# docking_station_with_STLink.net
KiCad netlist of a schematic drawn in Altium Designer
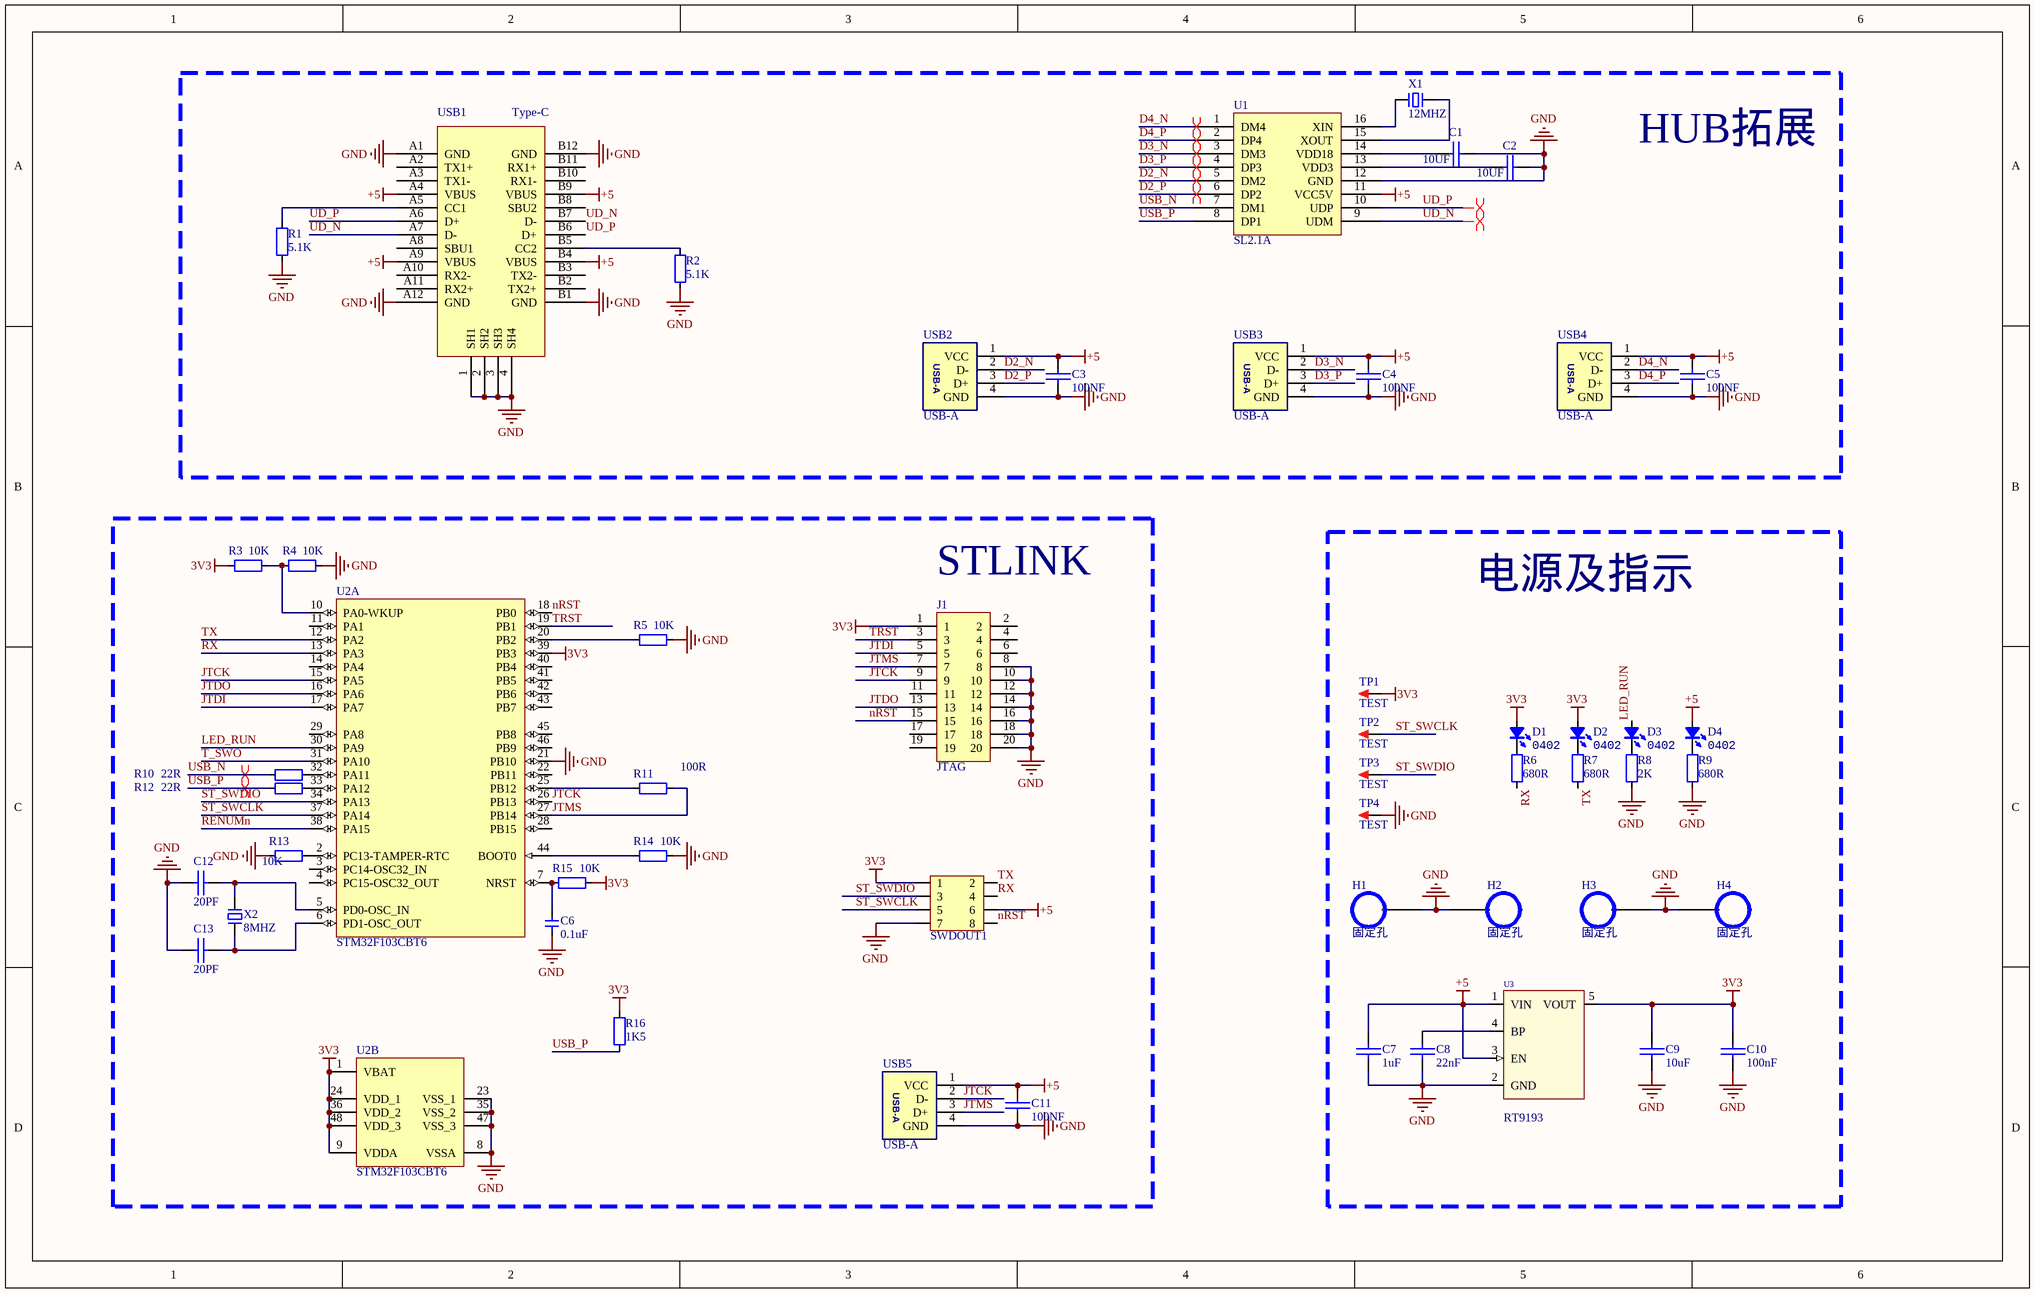
[diagram p0: docking_station_with_STLink.SchDoc]

(export (version "E")
  (design (tool "Eeschema 10.0.6"))
  (components
    (comp (ref "C1")
      (value "10UF")
      (footprint "0603C")
      (description "无极性电容")
      (libsource (lib "电容") (part "CAP"))
    )
    (comp (ref "C2")
      (value "10UF")
      (footprint "0603C")
      (description "无极性电容")
      (libsource (lib "电容") (part "CAP"))
    )
    (comp (ref "C3")
      (value "100NF")
      (footprint "0603C")
      (description "无极性电容")
      (libsource (lib "电容") (part "CAP"))
    )
    (comp (ref "C4")
      (value "100NF")
      (footprint "0603C")
      (description "无极性电容")
      (libsource (lib "电容") (part "CAP"))
    )
    (comp (ref "C5")
      (value "100NF")
      (footprint "0603C")
      (description "无极性电容")
      (libsource (lib "电容") (part "CAP"))
    )
    (comp (ref "C6")
      (value "0.1uF")
      (footprint "0603C")
      (description "Capacitor")
      (libsource (lib "MyPcbLib") (part "电容-0402"))
    )
    (comp (ref "C7")
      (value "1uF")
      (footprint "0603C")
      (description "无极性电容")
      (libsource (lib "电容") (part "CAP"))
    )
    (comp (ref "C8")
      (value "22nF")
      (footprint "0603C")
      (description "无极性电容")
      (libsource (lib "电容") (part "CAP"))
    )
    (comp (ref "C9")
      (value "10uF")
      (footprint "0603C")
      (description "无极性电容")
      (libsource (lib "电容") (part "CAP"))
    )
    (comp (ref "C10")
      (value "100nF")
      (footprint "0603C")
      (description "无极性电容")
      (libsource (lib "电容") (part "CAP"))
    )
    (comp (ref "C11")
      (value "100NF")
      (footprint "0603C")
      (description "无极性电容")
      (libsource (lib "电容") (part "CAP"))
    )
    (comp (ref "C12")
      (value "20PF")
      (footprint "0603C")
      (description "无极性电容")
      (libsource (lib "电容") (part "CAP"))
    )
    (comp (ref "C13")
      (value "20PF")
      (footprint "0603C")
      (description "无极性电容")
      (libsource (lib "电容") (part "CAP"))
    )
    (comp (ref "D1")
      (value "color?")
      (footprint "LED 0603B")
      (description "LED")
      (fields (field (name "TYPE") "0402"))
      (libsource (lib "KitSprout") (part "LED_0402"))
    )
    (comp (ref "D2")
      (value "color?")
      (footprint "LED 0603B")
      (description "LED")
      (fields (field (name "TYPE") "0402"))
      (libsource (lib "KitSprout") (part "LED_0402"))
    )
    (comp (ref "D3")
      (value "color?")
      (footprint "LED 0603B")
      (description "LED")
      (fields (field (name "TYPE") "0402"))
      (libsource (lib "KitSprout") (part "LED_0402"))
    )
    (comp (ref "D4")
      (value "color?")
      (footprint "LED 0603B")
      (description "LED")
      (fields (field (name "TYPE") "0402"))
      (libsource (lib "KitSprout") (part "LED_0402"))
    )
    (comp (ref "H1") (value "固定孔") (footprint "M3x4+6_N") (libsource (lib "固定柱") (part "固定孔")))
    (comp (ref "H2") (value "固定孔") (footprint "M3x4+6_N") (libsource (lib "固定柱") (part "固定孔")))
    (comp (ref "H3") (value "固定孔") (footprint "M3x4+6_N") (libsource (lib "固定柱") (part "固定孔")))
    (comp (ref "H4") (value "固定孔") (footprint "M3x4+6_N") (libsource (lib "固定柱") (part "固定孔")))
    (comp (ref "J1") (value "JTAG") (footprint "JLINK") (libsource (lib "排针") (part "Pin HDR2X10")))
    (comp (ref "R1")
      (value "5.1K")
      (footprint "0603R")
      (description "Resistor")
      (libsource (lib "") (part "电阻-0402_2"))
    )
    (comp (ref "R2")
      (value "5.1K")
      (footprint "0603R")
      (description "Resistor")
      (libsource (lib "") (part "电阻-0402_2"))
    )
    (comp (ref "R3")
      (value "10K")
      (footprint "0603R")
      (description "Resistor")
      (libsource (lib "") (part "电阻-0402_1"))
    )
    (comp (ref "R4")
      (value "10K")
      (footprint "0603R")
      (description "Resistor")
      (libsource (lib "") (part "电阻-0402_1"))
    )
    (comp (ref "R5")
      (value "10K")
      (footprint "0603R")
      (description "Resistor")
      (libsource (lib "") (part "电阻-0402_1"))
    )
    (comp (ref "R6")
      (value "680R")
      (footprint "0603R")
      (description "Resistor")
      (libsource (lib "MyPcbLib") (part "电阻-0402"))
    )
    (comp (ref "R7")
      (value "680R")
      (footprint "0603R")
      (description "Resistor")
      (libsource (lib "MyPcbLib") (part "电阻-0402"))
    )
    (comp (ref "R8")
      (value "2K")
      (footprint "0603R")
      (description "Resistor")
      (libsource (lib "MyPcbLib") (part "电阻-0402"))
    )
    (comp (ref "R9")
      (value "680R")
      (footprint "0603R")
      (description "Resistor")
      (libsource (lib "MyPcbLib") (part "电阻-0402"))
    )
    (comp (ref "R10")
      (value "22R")
      (footprint "0603R")
      (description "Resistor")
      (libsource (lib "") (part "电阻-0402_1"))
    )
    (comp (ref "R11")
      (value "100R")
      (footprint "0603R")
      (description "Resistor")
      (libsource (lib "") (part "电阻-0402_1"))
    )
    (comp (ref "R12")
      (value "22R")
      (footprint "0603R")
      (description "Resistor")
      (libsource (lib "") (part "电阻-0402_1"))
    )
    (comp (ref "R13")
      (value "10K")
      (footprint "0603R")
      (description "Resistor")
      (libsource (lib "") (part "电阻-0402_1"))
    )
    (comp (ref "R14")
      (value "10K")
      (footprint "0603R")
      (description "Resistor")
      (libsource (lib "") (part "电阻-0402_1"))
    )
    (comp (ref "R15")
      (value "10K")
      (footprint "0603R")
      (description "Resistor")
      (libsource (lib "") (part "电阻-0402_1"))
    )
    (comp (ref "R16")
      (value "1K5")
      (footprint "0603R")
      (description "Resistor")
      (libsource (lib "MyPcbLib") (part "电阻-0402"))
    )
    (comp (ref "SWDOUT1")
      (value "HDR2x4_2.54")
      (footprint "Pin HDR2X4/2.54mm-S")
      (description "Header")
      (libsource (lib "MyPcbLib") (part "HDR2x4_2.54"))
    )
    (comp (ref "TP1")
      (value "TEST")
      (footprint "TEST 1.6")
      (description "测试点")
      (libsource (lib "未分类IC") (part "TEST"))
    )
    (comp (ref "TP2")
      (value "TEST")
      (footprint "TEST 1.6")
      (description "测试点")
      (libsource (lib "未分类IC") (part "TEST"))
    )
    (comp (ref "TP3")
      (value "TEST")
      (footprint "TEST 1.6")
      (description "测试点")
      (libsource (lib "未分类IC") (part "TEST"))
    )
    (comp (ref "TP4")
      (value "TEST")
      (footprint "TEST 1.6")
      (description "测试点")
      (libsource (lib "未分类IC") (part "TEST"))
    )
    (comp (ref "U1")
      (value "SL2.1A")
      (footprint "SOP16")
      (description "USB2.0扩展")
      (libsource (lib "STM32系列") (part "SL2.1A"))
    )
    (comp (ref "U2")
      (value "STM32F103CBT6")
      (footprint "LQFP48 7X7")
      (libsource (lib "STMicroelectronics STM32 F1") (part "STM32F103CBT6"))
    )
    (comp (ref "U3")
      (value "RT9193")
      (footprint "SOT23-5")
      (fields (field (name "ICA_PARTNUM") "$$2191094$$RT9193-15CU5") (field (name "PART NUMBER") "TMP-13"))
      (libsource (lib "stm32蓝牙小车") (part "RT9193X_5P"))
    )
    (comp (ref "USB1")
      (value "Type-C")
      (footprint "TYPE-C-SMD_TYPE-C-24P-QCHT")
      (libsource (lib "MyPcbLib") (part "USB-Type-C-TOP"))
    )
    (comp (ref "USB2") (value "USB-A") (footprint "USB-A/S_A") (libsource (lib "USB") (part "USB-A")))
    (comp (ref "USB3") (value "USB-A") (footprint "USB-A/S_A") (libsource (lib "USB") (part "USB-A")))
    (comp (ref "USB4") (value "USB-A") (footprint "USB-A/S_A") (libsource (lib "USB") (part "USB-A")))
    (comp (ref "USB5") (value "USB-A") (footprint "USB-A/S_A") (libsource (lib "USB") (part "USB-A")))
    (comp (ref "X1")
      (value "12MHZ")
      (footprint "OSC HC-49S")
      (description "2脚无源脚晶振")
      (libsource (lib "晶振") (part "XTAL-2P"))
    )
    (comp (ref "X2")
      (value "8MHZ")
      (footprint "OSC HC-49SMD")
      (description "2脚无源脚晶振")
      (libsource (lib "晶振") (part "XTAL-2P"))
    )
  )
  (nets
    (net (code "1") (name "+5") (class "Default")
      (node (ref "C11") (pin "2") (pinfunction "2_2") (pintype "passive"))
      (node (ref "C3") (pin "2") (pinfunction "2_2") (pintype "passive"))
      (node (ref "C4") (pin "2") (pinfunction "2_2") (pintype "passive"))
      (node (ref "C5") (pin "2") (pinfunction "2_2") (pintype "passive"))
      (node (ref "C7") (pin "2") (pinfunction "2_2") (pintype "passive"))
      (node (ref "D4") (pin "1") (pinfunction "A_1") (pintype "passive"))
      (node (ref "SWDOUT1") (pin "6") (pinfunction "6_6") (pintype "passive"))
      (node (ref "U1") (pin "11") (pinfunction "VCC5V_11") (pintype "passive"))
      (node (ref "U3") (pin "1") (pinfunction "VIN_1") (pintype "power_in"))
      (node (ref "U3") (pin "3") (pinfunction "EN_3") (pintype "input"))
      (node (ref "USB1") (pin "A4") (pinfunction "VBUS_A4") (pintype "passive"))
      (node (ref "USB1") (pin "A9") (pinfunction "VBUS_A9") (pintype "passive"))
      (node (ref "USB1") (pin "B4") (pinfunction "VBUS_B4") (pintype "passive"))
      (node (ref "USB1") (pin "B9") (pinfunction "VBUS_B9") (pintype "passive"))
      (node (ref "USB2") (pin "1") (pinfunction "VCC_1") (pintype "passive"))
      (node (ref "USB3") (pin "1") (pinfunction "VCC_1") (pintype "passive"))
      (node (ref "USB4") (pin "1") (pinfunction "VCC_1") (pintype "passive"))
      (node (ref "USB5") (pin "1") (pinfunction "VCC_1") (pintype "passive"))
    )
    (net (code "2") (name "/D2_N") (class "Default")
      (node (ref "U1") (pin "5") (pinfunction "DM2_5") (pintype "passive"))
      (node (ref "USB2") (pin "2") (pinfunction "D-_2") (pintype "passive"))
    )
    (net (code "3") (name "/D2_P") (class "Default")
      (node (ref "U1") (pin "6") (pinfunction "DP2_6") (pintype "passive"))
      (node (ref "USB2") (pin "3") (pinfunction "D+_3") (pintype "passive"))
    )
    (net (code "4") (name "/D3_N") (class "Default")
      (node (ref "U1") (pin "3") (pinfunction "DM3_3") (pintype "passive"))
      (node (ref "USB3") (pin "2") (pinfunction "D-_2") (pintype "passive"))
    )
    (net (code "5") (name "/D3_P") (class "Default")
      (node (ref "U1") (pin "4") (pinfunction "DP3_4") (pintype "passive"))
      (node (ref "USB3") (pin "3") (pinfunction "D+_3") (pintype "passive"))
    )
    (net (code "6") (name "/D4_N") (class "Default")
      (node (ref "U1") (pin "1") (pinfunction "DM4_1") (pintype "passive"))
      (node (ref "USB4") (pin "2") (pinfunction "D-_2") (pintype "passive"))
    )
    (net (code "7") (name "/D4_P") (class "Default")
      (node (ref "U1") (pin "2") (pinfunction "DP4_2") (pintype "passive"))
      (node (ref "USB4") (pin "3") (pinfunction "D+_3") (pintype "passive"))
    )
    (net (code "8") (name "/JTCK") (class "Default")
      (node (ref "J1") (pin "9") (pinfunction "9_9") (pintype "passive"))
      (node (ref "U2") (pin "15") (pinfunction "PA5_15") (pintype "bidirectional"))
      (node (ref "U2") (pin "26") (pinfunction "PB13_26") (pintype "bidirectional"))
      (node (ref "USB5") (pin "2") (pinfunction "D-_2") (pintype "passive"))
    )
    (net (code "9") (name "/JTDI") (class "Default")
      (node (ref "J1") (pin "5") (pinfunction "5_5") (pintype "passive"))
      (node (ref "U2") (pin "17") (pinfunction "PA7_17") (pintype "bidirectional"))
    )
    (net (code "10") (name "/JTDO") (class "Default")
      (node (ref "J1") (pin "13") (pinfunction "13_13") (pintype "passive"))
      (node (ref "U2") (pin "16") (pinfunction "PA6_16") (pintype "bidirectional"))
    )
    (net (code "11") (name "/JTMS") (class "Default")
      (node (ref "J1") (pin "7") (pinfunction "7_7") (pintype "passive"))
      (node (ref "R11") (pin "2") (pinfunction "2_2") (pintype "passive"))
      (node (ref "U2") (pin "27") (pinfunction "PB14_27") (pintype "bidirectional"))
      (node (ref "USB5") (pin "3") (pinfunction "D+_3") (pintype "passive"))
    )
    (net (code "12") (name "/LED_RUN") (class "Default")
      (node (ref "D3") (pin "1") (pinfunction "A_1") (pintype "passive"))
      (node (ref "U2") (pin "30") (pinfunction "PA9_30") (pintype "bidirectional"))
    )
    (net (code "13") (name "/RENUMn") (class "Default")
      (node (ref "U2") (pin "38") (pinfunction "PA15_38") (pintype "bidirectional"))
    )
    (net (code "14") (name "/RX") (class "Default")
      (node (ref "R6") (pin "1") (pinfunction "1_1") (pintype "passive"))
      (node (ref "SWDOUT1") (pin "4") (pinfunction "4_4") (pintype "passive"))
      (node (ref "U2") (pin "13") (pinfunction "PA3_13") (pintype "bidirectional"))
    )
    (net (code "15") (name "/ST_SWCLK") (class "Default")
      (node (ref "SWDOUT1") (pin "5") (pinfunction "5_5") (pintype "passive"))
      (node (ref "TP2") (pin "1") (pinfunction "1_1") (pintype "passive"))
      (node (ref "U2") (pin "37") (pinfunction "PA14_37") (pintype "bidirectional"))
    )
    (net (code "16") (name "/ST_SWDIO") (class "Default")
      (node (ref "SWDOUT1") (pin "3") (pinfunction "3_3") (pintype "passive"))
      (node (ref "TP3") (pin "1") (pinfunction "1_1") (pintype "passive"))
      (node (ref "U2") (pin "34") (pinfunction "PA13_34") (pintype "bidirectional"))
    )
    (net (code "17") (name "/TRST") (class "Default")
      (node (ref "J1") (pin "3") (pinfunction "3_3") (pintype "passive"))
      (node (ref "U2") (pin "19") (pinfunction "PB1_19") (pintype "bidirectional"))
    )
    (net (code "18") (name "/TX") (class "Default")
      (node (ref "R7") (pin "1") (pinfunction "1_1") (pintype "passive"))
      (node (ref "SWDOUT1") (pin "2") (pinfunction "2_2") (pintype "passive"))
      (node (ref "U2") (pin "12") (pinfunction "PA2_12") (pintype "bidirectional"))
    )
    (net (code "19") (name "/T_SWO") (class "Default")
      (node (ref "U2") (pin "31") (pinfunction "PA10_31") (pintype "bidirectional"))
    )
    (net (code "20") (name "/UD_N") (class "Default")
      (node (ref "U1") (pin "9") (pinfunction "UDM_9") (pintype "passive"))
      (node (ref "USB1") (pin "A7") (pinfunction "D-_A7") (pintype "passive"))
      (node (ref "USB1") (pin "B7") (pinfunction "D-_B7") (pintype "passive"))
    )
    (net (code "21") (name "/UD_P") (class "Default")
      (node (ref "U1") (pin "10") (pinfunction "UDP_10") (pintype "passive"))
      (node (ref "USB1") (pin "A6") (pinfunction "D+_A6") (pintype "passive"))
      (node (ref "USB1") (pin "B6") (pinfunction "D+_B6") (pintype "passive"))
    )
    (net (code "22") (name "/USB_N") (class "Default")
      (node (ref "R10") (pin "1") (pinfunction "1_1") (pintype "passive"))
      (node (ref "U1") (pin "7") (pinfunction "DM1_7") (pintype "passive"))
    )
    (net (code "23") (name "/USB_P") (class "Default")
      (node (ref "R12") (pin "1") (pinfunction "1_1") (pintype "passive"))
      (node (ref "R16") (pin "1") (pinfunction "1_1") (pintype "passive"))
      (node (ref "U1") (pin "8") (pinfunction "DP1_8") (pintype "passive"))
    )
    (net (code "24") (name "/nRST") (class "Default")
      (node (ref "J1") (pin "15") (pinfunction "15_15") (pintype "passive"))
      (node (ref "SWDOUT1") (pin "8") (pinfunction "8_8") (pintype "passive"))
      (node (ref "U2") (pin "18") (pinfunction "PB0_18") (pintype "bidirectional"))
    )
    (net (code "25") (name "3V3") (class "Default")
      (node (ref "C10") (pin "2") (pinfunction "2_2") (pintype "passive"))
      (node (ref "C9") (pin "2") (pinfunction "2_2") (pintype "passive"))
      (node (ref "D1") (pin "1") (pinfunction "A_1") (pintype "passive"))
      (node (ref "D2") (pin "1") (pinfunction "A_1") (pintype "passive"))
      (node (ref "J1") (pin "1") (pinfunction "1_1") (pintype "passive"))
      (node (ref "R15") (pin "2") (pinfunction "2_2") (pintype "passive"))
      (node (ref "R16") (pin "2") (pinfunction "2_2") (pintype "passive"))
      (node (ref "R3") (pin "1") (pinfunction "1_1") (pintype "passive"))
      (node (ref "SWDOUT1") (pin "1") (pinfunction "1_1") (pintype "passive"))
      (node (ref "TP1") (pin "1") (pinfunction "1_1") (pintype "passive"))
      (node (ref "U2") (pin "1") (pinfunction "VBAT_1") (pintype "power_in"))
      (node (ref "U2") (pin "24") (pinfunction "VDD_1_24") (pintype "power_in"))
      (node (ref "U2") (pin "36") (pinfunction "VDD_2_36") (pintype "power_in"))
      (node (ref "U2") (pin "39") (pinfunction "PB3_39") (pintype "bidirectional"))
      (node (ref "U2") (pin "48") (pinfunction "VDD_3_48") (pintype "power_in"))
      (node (ref "U2") (pin "9") (pinfunction "VDDA_9") (pintype "power_in"))
      (node (ref "U3") (pin "5") (pinfunction "VOUT_5") (pintype "power_in"))
    )
    (net (code "26") (name "GND") (class "Default")
      (node (ref "C1") (pin "2") (pinfunction "2_2") (pintype "passive"))
      (node (ref "C10") (pin "1") (pinfunction "1_1") (pintype "passive"))
      (node (ref "C11") (pin "1") (pinfunction "1_1") (pintype "passive"))
      (node (ref "C12") (pin "2") (pinfunction "2_2") (pintype "passive"))
      (node (ref "C13") (pin "2") (pinfunction "2_2") (pintype "passive"))
      (node (ref "C2") (pin "2") (pinfunction "2_2") (pintype "passive"))
      (node (ref "C3") (pin "1") (pinfunction "1_1") (pintype "passive"))
      (node (ref "C4") (pin "1") (pinfunction "1_1") (pintype "passive"))
      (node (ref "C5") (pin "1") (pinfunction "1_1") (pintype "passive"))
      (node (ref "C6") (pin "1") (pinfunction "1_1") (pintype "passive"))
      (node (ref "C7") (pin "1") (pinfunction "1_1") (pintype "passive"))
      (node (ref "C8") (pin "1") (pinfunction "1_1") (pintype "passive"))
      (node (ref "C9") (pin "1") (pinfunction "1_1") (pintype "passive"))
      (node (ref "H1") (pin "1") (pinfunction "1_1") (pintype "passive"))
      (node (ref "H2") (pin "1") (pinfunction "1_1") (pintype "passive"))
      (node (ref "H3") (pin "1") (pinfunction "1_1") (pintype "passive"))
      (node (ref "H4") (pin "1") (pinfunction "1_1") (pintype "passive"))
      (node (ref "J1") (pin "10") (pinfunction "10_10") (pintype "passive"))
      (node (ref "J1") (pin "12") (pinfunction "12_12") (pintype "passive"))
      (node (ref "J1") (pin "14") (pinfunction "14_14") (pintype "passive"))
      (node (ref "J1") (pin "16") (pinfunction "16_16") (pintype "passive"))
      (node (ref "J1") (pin "18") (pinfunction "18_18") (pintype "passive"))
      (node (ref "J1") (pin "20") (pinfunction "20_20") (pintype "passive"))
      (node (ref "J1") (pin "8") (pinfunction "8_8") (pintype "passive"))
      (node (ref "R1") (pin "2") (pinfunction "2_2") (pintype "passive"))
      (node (ref "R13") (pin "1") (pinfunction "1_1") (pintype "passive"))
      (node (ref "R14") (pin "2") (pinfunction "2_2") (pintype "passive"))
      (node (ref "R2") (pin "2") (pinfunction "2_2") (pintype "passive"))
      (node (ref "R4") (pin "2") (pinfunction "2_2") (pintype "passive"))
      (node (ref "R5") (pin "2") (pinfunction "2_2") (pintype "passive"))
      (node (ref "R8") (pin "1") (pinfunction "1_1") (pintype "passive"))
      (node (ref "R9") (pin "1") (pinfunction "1_1") (pintype "passive"))
      (node (ref "SWDOUT1") (pin "7") (pinfunction "7_7") (pintype "passive"))
      (node (ref "TP4") (pin "1") (pinfunction "1_1") (pintype "passive"))
      (node (ref "U1") (pin "12") (pinfunction "GND_12") (pintype "passive"))
      (node (ref "U2") (pin "21") (pinfunction "PB10_21") (pintype "bidirectional"))
      (node (ref "U2") (pin "23") (pinfunction "VSS_1_23") (pintype "power_in"))
      (node (ref "U2") (pin "35") (pinfunction "VSS_2_35") (pintype "power_in"))
      (node (ref "U2") (pin "47") (pinfunction "VSS_3_47") (pintype "power_in"))
      (node (ref "U2") (pin "8") (pinfunction "VSSA_8") (pintype "power_in"))
      (node (ref "U3") (pin "2") (pinfunction "GND_2") (pintype "power_in"))
      (node (ref "USB1") (pin "1") (pinfunction "SH1_1") (pintype "passive"))
      (node (ref "USB1") (pin "2") (pinfunction "SH2_2") (pintype "passive"))
      (node (ref "USB1") (pin "3") (pinfunction "SH3_3") (pintype "passive"))
      (node (ref "USB1") (pin "4") (pinfunction "SH4_4") (pintype "passive"))
      (node (ref "USB1") (pin "A1") (pinfunction "GND_A1") (pintype "passive"))
      (node (ref "USB1") (pin "A12") (pinfunction "GND_A12") (pintype "passive"))
      (node (ref "USB1") (pin "B1") (pinfunction "GND_B1") (pintype "passive"))
      (node (ref "USB1") (pin "B12") (pinfunction "GND_B12") (pintype "passive"))
      (node (ref "USB2") (pin "4") (pinfunction "GND_4") (pintype "passive"))
      (node (ref "USB3") (pin "4") (pinfunction "GND_4") (pintype "passive"))
      (node (ref "USB4") (pin "4") (pinfunction "GND_4") (pintype "passive"))
      (node (ref "USB5") (pin "4") (pinfunction "GND_4") (pintype "passive"))
    )
    (net (code "27") (name "Net-(D1-K)") (class "Default")
      (node (ref "D1") (pin "2") (pinfunction "K_2") (pintype "passive"))
      (node (ref "R6") (pin "2") (pinfunction "2_2") (pintype "passive"))
    )
    (net (code "28") (name "Net-(D2-K)") (class "Default")
      (node (ref "D2") (pin "2") (pinfunction "K_2") (pintype "passive"))
      (node (ref "R7") (pin "2") (pinfunction "2_2") (pintype "passive"))
    )
    (net (code "29") (name "Net-(D3-K)") (class "Default")
      (node (ref "D3") (pin "2") (pinfunction "K_2") (pintype "passive"))
      (node (ref "R8") (pin "2") (pinfunction "2_2") (pintype "passive"))
    )
    (net (code "30") (name "Net-(D4-K)") (class "Default")
      (node (ref "D4") (pin "2") (pinfunction "K_2") (pintype "passive"))
      (node (ref "R9") (pin "2") (pinfunction "2_2") (pintype "passive"))
    )
    (net (code "31") (name "Net-(U1-VDD3)") (class "Default")
      (node (ref "C2") (pin "1") (pinfunction "1_1") (pintype "passive"))
      (node (ref "U1") (pin "13") (pinfunction "VDD3_13") (pintype "passive"))
    )
    (net (code "32") (name "Net-(U1-VDD18)") (class "Default")
      (node (ref "C1") (pin "1") (pinfunction "1_1") (pintype "passive"))
      (node (ref "U1") (pin "14") (pinfunction "VDD18_14") (pintype "passive"))
    )
    (net (code "33") (name "Net-(U1-XIN)") (class "Default")
      (node (ref "U1") (pin "16") (pinfunction "XIN_16") (pintype "passive"))
      (node (ref "X1") (pin "2") (pinfunction "2_2") (pintype "passive"))
    )
    (net (code "34") (name "Net-(U1-XOUT)") (class "Default")
      (node (ref "U1") (pin "15") (pinfunction "XOUT_15") (pintype "passive"))
      (node (ref "X1") (pin "1") (pinfunction "1_1") (pintype "passive"))
    )
    (net (code "35") (name "Net-(U2A-BOOT0)") (class "Default")
      (node (ref "R14") (pin "1") (pinfunction "1_1") (pintype "passive"))
      (node (ref "U2") (pin "44") (pinfunction "BOOT0_44") (pintype "input"))
    )
    (net (code "36") (name "Net-(U2A-NRST)") (class "Default")
      (node (ref "C6") (pin "2") (pinfunction "2_2") (pintype "passive"))
      (node (ref "R15") (pin "1") (pinfunction "1_1") (pintype "passive"))
      (node (ref "U2") (pin "7") (pinfunction "NRST_7") (pintype "bidirectional"))
    )
    (net (code "37") (name "Net-(U2A-PA0-WKUP)") (class "Default")
      (node (ref "R3") (pin "2") (pinfunction "2_2") (pintype "passive"))
      (node (ref "R4") (pin "1") (pinfunction "1_1") (pintype "passive"))
      (node (ref "U2") (pin "10") (pinfunction "PA0-WKUP_10") (pintype "bidirectional"))
    )
    (net (code "38") (name "Net-(U2A-PA11)") (class "Default")
      (node (ref "R10") (pin "2") (pinfunction "2_2") (pintype "passive"))
      (node (ref "U2") (pin "32") (pinfunction "PA11_32") (pintype "bidirectional"))
    )
    (net (code "39") (name "Net-(U2A-PA12)") (class "Default")
      (node (ref "R12") (pin "2") (pinfunction "2_2") (pintype "passive"))
      (node (ref "U2") (pin "33") (pinfunction "PA12_33") (pintype "bidirectional"))
    )
    (net (code "40") (name "Net-(U2A-PB2)") (class "Default")
      (node (ref "R5") (pin "1") (pinfunction "1_1") (pintype "passive"))
      (node (ref "U2") (pin "20") (pinfunction "PB2_20") (pintype "bidirectional"))
    )
    (net (code "41") (name "Net-(U2A-PB12)") (class "Default")
      (node (ref "R11") (pin "1") (pinfunction "1_1") (pintype "passive"))
      (node (ref "U2") (pin "25") (pinfunction "PB12_25") (pintype "bidirectional"))
    )
    (net (code "42") (name "Net-(U2A-PC13-TAMPER-RTC)") (class "Default")
      (node (ref "R13") (pin "2") (pinfunction "2_2") (pintype "passive"))
      (node (ref "U2") (pin "2") (pinfunction "PC13-TAMPER-RTC_2") (pintype "bidirectional"))
    )
    (net (code "43") (name "Net-(U2A-PD0-OSC_IN)") (class "Default")
      (node (ref "C12") (pin "1") (pinfunction "1_1") (pintype "passive"))
      (node (ref "U2") (pin "5") (pinfunction "PD0-OSC_IN_5") (pintype "bidirectional"))
      (node (ref "X2") (pin "1") (pinfunction "1_1") (pintype "passive"))
    )
    (net (code "44") (name "Net-(U2A-PD1-OSC_OUT)") (class "Default")
      (node (ref "C13") (pin "1") (pinfunction "1_1") (pintype "passive"))
      (node (ref "U2") (pin "6") (pinfunction "PD1-OSC_OUT_6") (pintype "bidirectional"))
      (node (ref "X2") (pin "2") (pinfunction "2_2") (pintype "passive"))
    )
    (net (code "45") (name "Net-(U3-BP)") (class "Default")
      (node (ref "C8") (pin "2") (pinfunction "2_2") (pintype "passive"))
      (node (ref "U3") (pin "4") (pinfunction "BP_4") (pintype "passive"))
    )
    (net (code "46") (name "Net-(USB1-CC1)") (class "Default")
      (node (ref "R1") (pin "1") (pinfunction "1_1") (pintype "passive"))
      (node (ref "USB1") (pin "A5") (pinfunction "CC1_A5") (pintype "passive"))
    )
    (net (code "47") (name "Net-(USB1-CC2)") (class "Default")
      (node (ref "R2") (pin "1") (pinfunction "1_1") (pintype "passive"))
      (node (ref "USB1") (pin "B5") (pinfunction "CC2_B5") (pintype "passive"))
    )
    (net (code "48") (name "unconnected-(J1-Pad2)") (class "Default")
      (node (ref "J1") (pin "2") (pinfunction "2_2") (pintype "passive"))
    )
    (net (code "49") (name "unconnected-(J1-Pad4)") (class "Default")
      (node (ref "J1") (pin "4") (pinfunction "4_4") (pintype "passive"))
    )
    (net (code "50") (name "unconnected-(J1-Pad6)") (class "Default")
      (node (ref "J1") (pin "6") (pinfunction "6_6") (pintype "passive"))
    )
    (net (code "51") (name "unconnected-(J1-Pad11)") (class "Default")
      (node (ref "J1") (pin "11") (pinfunction "11_11") (pintype "passive"))
    )
    (net (code "52") (name "unconnected-(J1-Pad17)") (class "Default")
      (node (ref "J1") (pin "17") (pinfunction "17_17") (pintype "passive"))
    )
    (net (code "53") (name "unconnected-(J1-Pad19)") (class "Default")
      (node (ref "J1") (pin "19") (pinfunction "19_19") (pintype "passive"))
    )
    (net (code "54") (name "unconnected-(U2A-PA1-Pad11)") (class "Default")
      (node (ref "U2") (pin "11") (pinfunction "PA1_11") (pintype "bidirectional"))
    )
    (net (code "55") (name "unconnected-(U2A-PA4-Pad14)") (class "Default")
      (node (ref "U2") (pin "14") (pinfunction "PA4_14") (pintype "bidirectional"))
    )
    (net (code "56") (name "unconnected-(U2A-PA8-Pad29)") (class "Default")
      (node (ref "U2") (pin "29") (pinfunction "PA8_29") (pintype "bidirectional"))
    )
    (net (code "57") (name "unconnected-(U2A-PB4-Pad40)") (class "Default")
      (node (ref "U2") (pin "40") (pinfunction "PB4_40") (pintype "bidirectional"))
    )
    (net (code "58") (name "unconnected-(U2A-PB5-Pad41)") (class "Default")
      (node (ref "U2") (pin "41") (pinfunction "PB5_41") (pintype "bidirectional"))
    )
    (net (code "59") (name "unconnected-(U2A-PB6-Pad42)") (class "Default")
      (node (ref "U2") (pin "42") (pinfunction "PB6_42") (pintype "bidirectional"))
    )
    (net (code "60") (name "unconnected-(U2A-PB7-Pad43)") (class "Default")
      (node (ref "U2") (pin "43") (pinfunction "PB7_43") (pintype "bidirectional"))
    )
    (net (code "61") (name "unconnected-(U2A-PB8-Pad45)") (class "Default")
      (node (ref "U2") (pin "45") (pinfunction "PB8_45") (pintype "bidirectional"))
    )
    (net (code "62") (name "unconnected-(U2A-PB9-Pad46)") (class "Default")
      (node (ref "U2") (pin "46") (pinfunction "PB9_46") (pintype "bidirectional"))
    )
    (net (code "63") (name "unconnected-(U2A-PB11-Pad22)") (class "Default")
      (node (ref "U2") (pin "22") (pinfunction "PB11_22") (pintype "bidirectional"))
    )
    (net (code "64") (name "unconnected-(U2A-PB15-Pad28)") (class "Default")
      (node (ref "U2") (pin "28") (pinfunction "PB15_28") (pintype "bidirectional"))
    )
    (net (code "65") (name "unconnected-(U2A-PC14-OSC32_IN-Pad3)") (class "Default")
      (node (ref "U2") (pin "3") (pinfunction "PC14-OSC32_IN_3") (pintype "bidirectional"))
    )
    (net (code "66") (name "unconnected-(U2A-PC15-OSC32_OUT-Pad4)") (class "Default")
      (node (ref "U2") (pin "4") (pinfunction "PC15-OSC32_OUT_4") (pintype "bidirectional"))
    )
    (net (code "67") (name "unconnected-(USB1-RX1+-PadB11)") (class "Default")
      (node (ref "USB1") (pin "B11") (pinfunction "RX1+_B11") (pintype "passive"))
    )
    (net (code "68") (name "unconnected-(USB1-RX1--PadB10)") (class "Default")
      (node (ref "USB1") (pin "B10") (pinfunction "RX1-_B10") (pintype "passive"))
    )
    (net (code "69") (name "unconnected-(USB1-RX2+-PadA11)") (class "Default")
      (node (ref "USB1") (pin "A11") (pinfunction "RX2+_A11") (pintype "passive"))
    )
    (net (code "70") (name "unconnected-(USB1-RX2--PadA10)") (class "Default")
      (node (ref "USB1") (pin "A10") (pinfunction "RX2-_A10") (pintype "passive"))
    )
    (net (code "71") (name "unconnected-(USB1-SBU1-PadA8)") (class "Default")
      (node (ref "USB1") (pin "A8") (pinfunction "SBU1_A8") (pintype "passive"))
    )
    (net (code "72") (name "unconnected-(USB1-SBU2-PadB8)") (class "Default")
      (node (ref "USB1") (pin "B8") (pinfunction "SBU2_B8") (pintype "passive"))
    )
    (net (code "73") (name "unconnected-(USB1-TX1+-PadA2)") (class "Default")
      (node (ref "USB1") (pin "A2") (pinfunction "TX1+_A2") (pintype "passive"))
    )
    (net (code "74") (name "unconnected-(USB1-TX1--PadA3)") (class "Default")
      (node (ref "USB1") (pin "A3") (pinfunction "TX1-_A3") (pintype "passive"))
    )
    (net (code "75") (name "unconnected-(USB1-TX2+-PadB2)") (class "Default")
      (node (ref "USB1") (pin "B2") (pinfunction "TX2+_B2") (pintype "passive"))
    )
    (net (code "76") (name "unconnected-(USB1-TX2--PadB3)") (class "Default")
      (node (ref "USB1") (pin "B3") (pinfunction "TX2-_B3") (pintype "passive"))
    )
  )
)
